# SIM800A.net
KiCad netlist of a schematic drawn in Altium Designer
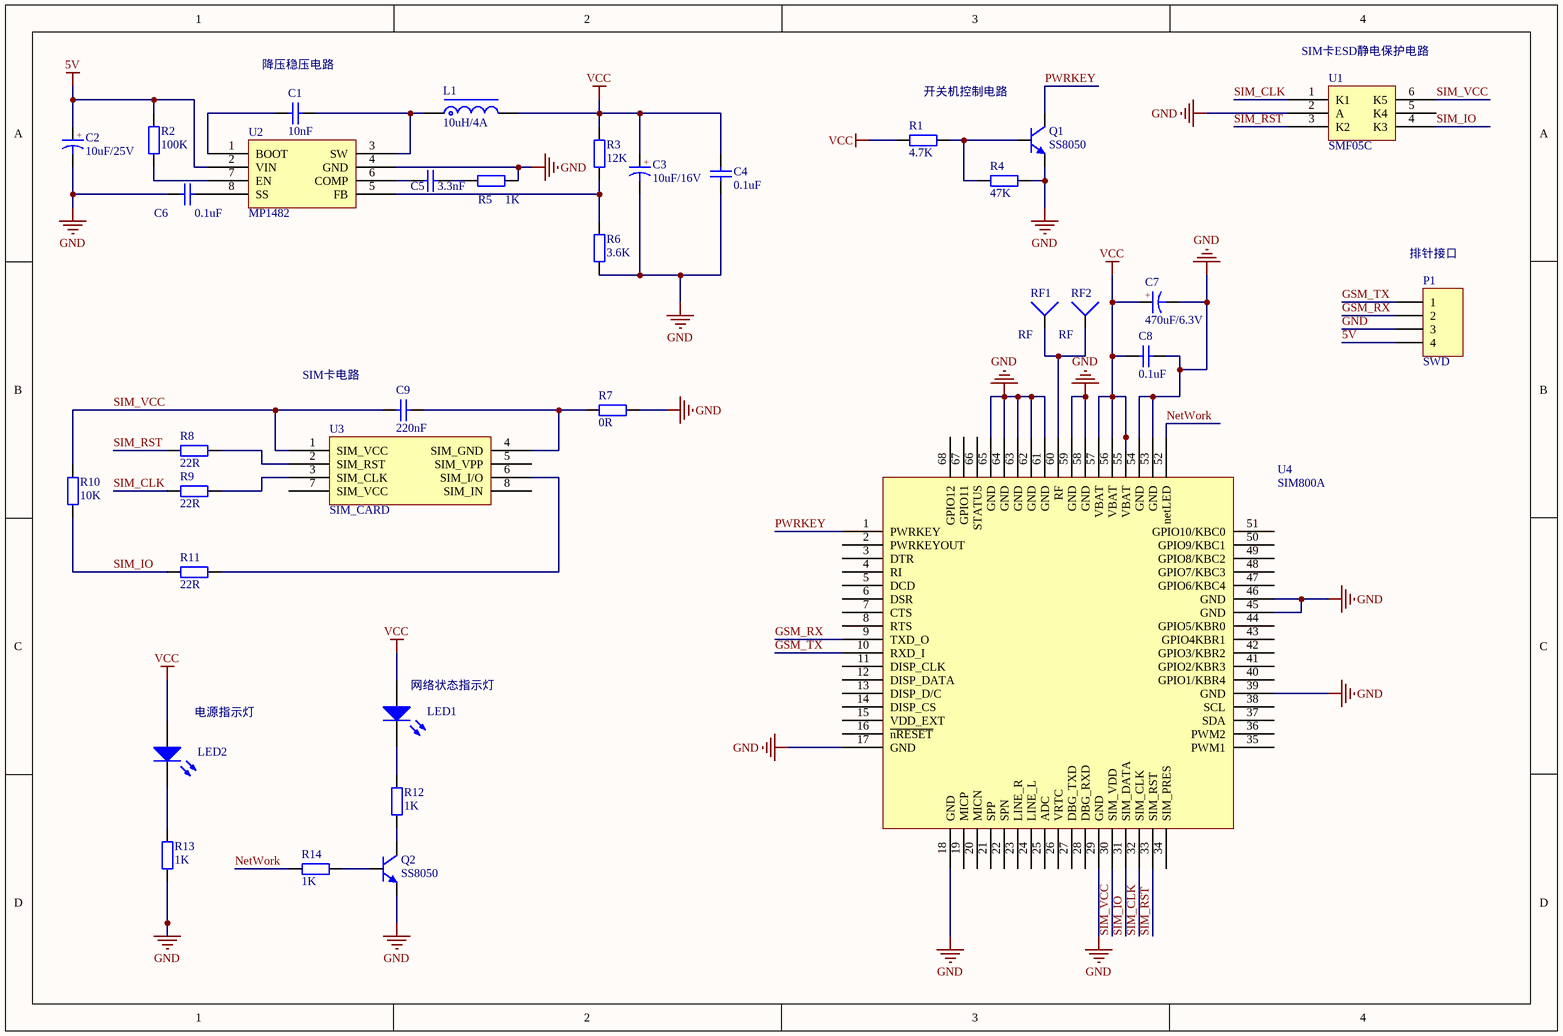
[diagram p0: SIM800A.SchDoc]

(export (version "E")
  (design (tool "Eeschema 10.0.6"))
  (components
    (comp (ref "C1")
      (value "10nF")
      (footprint "C0805_L")
      (description "贴片电容/MLCC电容")
      (libsource (lib "0.1 - 电阻-电容-电感-保险丝-晶振-晶体-磁珠-电位器-法拉电容-馈通电容") (part "C"))
    )
    (comp (ref "C2")
      (value "10uF/25V")
      (footprint "CE-1.5*4*8")
      (description "直插电解电容")
      (libsource (lib "0.1 - 电阻-电容-电感-保险丝-晶振-晶体-磁珠-电位器-法拉电容-馈通电容") (part "CE"))
    )
    (comp (ref "C3")
      (value "10uF/16V")
      (footprint "CE-1.5*4*8")
      (description "直插电解电容")
      (libsource (lib "0.1 - 电阻-电容-电感-保险丝-晶振-晶体-磁珠-电位器-法拉电容-馈通电容") (part "CE"))
    )
    (comp (ref "C4")
      (value "0.1uF")
      (footprint "C0805_L")
      (description "贴片电容/MLCC电容")
      (libsource (lib "0.1 - 电阻-电容-电感-保险丝-晶振-晶体-磁珠-电位器-法拉电容-馈通电容") (part "C"))
    )
    (comp (ref "C5")
      (value "3.3nF")
      (footprint "C0805_L")
      (description "贴片电容/MLCC电容")
      (libsource (lib "0.1 - 电阻-电容-电感-保险丝-晶振-晶体-磁珠-电位器-法拉电容-馈通电容") (part "C"))
    )
    (comp (ref "C6")
      (value "0.1uF")
      (footprint "C0805_L")
      (description "贴片电容/MLCC电容")
      (libsource (lib "0.1 - 电阻-电容-电感-保险丝-晶振-晶体-磁珠-电位器-法拉电容-馈通电容") (part "C"))
    )
    (comp (ref "C7")
      (value "470uF/6.3V")
      (footprint "CE-1.5*4*8")
      (description "直插电解电容")
      (libsource (lib "0.1 - 电阻-电容-电感-保险丝-晶振-晶体-磁珠-电位器-法拉电容-馈通电容") (part "CE"))
    )
    (comp (ref "C8")
      (value "0.1uF")
      (footprint "C0805_L")
      (description "贴片电容/MLCC电容")
      (libsource (lib "0.1 - 电阻-电容-电感-保险丝-晶振-晶体-磁珠-电位器-法拉电容-馈通电容") (part "C"))
    )
    (comp (ref "C9")
      (value "220nF")
      (footprint "C0805_L")
      (description "贴片电容/MLCC电容")
      (libsource (lib "0.1 - 电阻-电容-电感-保险丝-晶振-晶体-磁珠-电位器-法拉电容-馈通电容") (part "C"))
    )
    (comp (ref "L1")
      (value "10uH/4A")
      (footprint "LMR135")
      (description "功率磁环电感")
      (libsource (lib "0.1 - 电阻-电容-电感-保险丝-晶振-晶体-磁珠-电位器-法拉电容-馈通电容") (part "L-MR"))
    )
    (comp (ref "LED1")
      (value "红色")
      (footprint "LED0805_G")
      (description "贴片LED")
      (libsource (lib "0.3 - LED发光二极管-IR二极管_接收管-光耦") (part "LED"))
    )
    (comp (ref "LED2")
      (value "红色")
      (footprint "LED0805_G")
      (description "贴片LED")
      (libsource (lib "0.3 - LED发光二极管-IR二极管_接收管-光耦") (part "LED"))
    )
    (comp (ref "P1")
      (value "SWD")
      (footprint "HDR1X4")
      (description "Header, 4-Pin")
      (fields (field (name "PUBLISHER") "Altium Limited"))
      (libsource (lib "STM32F103C8T6") (part "Header 4"))
    )
    (comp (ref "Q1")
      (value "SS8050")
      (footprint "TO92A")
      (description "高频放大-NPN型")
      (libsource (lib "0.4 - 三极管-场效应管-可控硅") (part "8050-DIP"))
    )
    (comp (ref "Q2")
      (value "SS8050")
      (footprint "TO92A")
      (description "高频放大-NPN型")
      (libsource (lib "0.4 - 三极管-场效应管-可控硅") (part "8050-DIP"))
    )
    (comp (ref "R1")
      (value "4.7K")
      (footprint "R0805_L")
      (description "贴片电阻")
      (libsource (lib "0.1 - 电阻-电容-电感-保险丝-晶振-晶体-磁珠-电位器-法拉电容-馈通电容") (part "R"))
    )
    (comp (ref "R2")
      (value "100K")
      (footprint "R0805_L")
      (description "贴片电阻")
      (libsource (lib "0.1 - 电阻-电容-电感-保险丝-晶振-晶体-磁珠-电位器-法拉电容-馈通电容") (part "R"))
    )
    (comp (ref "R3")
      (value "12K")
      (footprint "R0805_L")
      (description "贴片电阻")
      (libsource (lib "0.1 - 电阻-电容-电感-保险丝-晶振-晶体-磁珠-电位器-法拉电容-馈通电容") (part "R"))
    )
    (comp (ref "R4")
      (value "47K")
      (footprint "R0805_L")
      (description "贴片电阻")
      (libsource (lib "0.1 - 电阻-电容-电感-保险丝-晶振-晶体-磁珠-电位器-法拉电容-馈通电容") (part "R"))
    )
    (comp (ref "R5")
      (value "1K")
      (footprint "R0805_L")
      (description "贴片电阻")
      (libsource (lib "0.1 - 电阻-电容-电感-保险丝-晶振-晶体-磁珠-电位器-法拉电容-馈通电容") (part "R"))
    )
    (comp (ref "R6")
      (value "3.6K")
      (footprint "R0805_L")
      (description "贴片电阻")
      (libsource (lib "0.1 - 电阻-电容-电感-保险丝-晶振-晶体-磁珠-电位器-法拉电容-馈通电容") (part "R"))
    )
    (comp (ref "R7")
      (value "0R")
      (footprint "R0805_L")
      (description "贴片电阻")
      (libsource (lib "0.1 - 电阻-电容-电感-保险丝-晶振-晶体-磁珠-电位器-法拉电容-馈通电容") (part "R"))
    )
    (comp (ref "R8")
      (value "22R")
      (footprint "R0805_L")
      (description "贴片电阻")
      (libsource (lib "0.1 - 电阻-电容-电感-保险丝-晶振-晶体-磁珠-电位器-法拉电容-馈通电容") (part "R"))
    )
    (comp (ref "R9")
      (value "22R")
      (footprint "R0805_L")
      (description "贴片电阻")
      (libsource (lib "0.1 - 电阻-电容-电感-保险丝-晶振-晶体-磁珠-电位器-法拉电容-馈通电容") (part "R"))
    )
    (comp (ref "R10")
      (value "10K")
      (footprint "R0805_L")
      (description "贴片电阻")
      (libsource (lib "0.1 - 电阻-电容-电感-保险丝-晶振-晶体-磁珠-电位器-法拉电容-馈通电容") (part "R"))
    )
    (comp (ref "R11")
      (value "22R")
      (footprint "R0805_L")
      (description "贴片电阻")
      (libsource (lib "0.1 - 电阻-电容-电感-保险丝-晶振-晶体-磁珠-电位器-法拉电容-馈通电容") (part "R"))
    )
    (comp (ref "R12")
      (value "1K")
      (footprint "R0805_L")
      (description "贴片电阻")
      (libsource (lib "0.1 - 电阻-电容-电感-保险丝-晶振-晶体-磁珠-电位器-法拉电容-馈通电容") (part "R"))
    )
    (comp (ref "R13")
      (value "1K")
      (footprint "R0805_L")
      (description "贴片电阻")
      (libsource (lib "0.1 - 电阻-电容-电感-保险丝-晶振-晶体-磁珠-电位器-法拉电容-馈通电容") (part "R"))
    )
    (comp (ref "R14")
      (value "1K")
      (footprint "R0805_L")
      (description "贴片电阻")
      (libsource (lib "0.1 - 电阻-电容-电感-保险丝-晶振-晶体-磁珠-电位器-法拉电容-馈通电容") (part "R"))
    )
    (comp (ref "RF1") (value "RF") (libsource (lib "SIM800A") (part "RF")))
    (comp (ref "RF2") (value "RF") (libsource (lib "SIM800A") (part "RF")))
    (comp (ref "U1") (value "SMF05C") (libsource (lib "SIM800A") (part "SMF05C")))
    (comp (ref "U2") (value "MP1482") (libsource (lib "SIM800A") (part "MP1482")))
    (comp (ref "U3") (value "SIM_CARD") (libsource (lib "SIM800A") (part "SIM_CARD")))
    (comp (ref "U4") (value "SIM800A") (libsource (lib "SIM800A") (part "SIM800A")))
  )
  (nets
    (net (code "1") (name "/GSM_RX") (class "Default")
      (node (ref "P1") (pin "2") (pinfunction "2_2") (pintype "passive"))
      (node (ref "U4") (pin "9") (pinfunction "TXD_O_9") (pintype "passive"))
    )
    (net (code "2") (name "/GSM_TX") (class "Default")
      (node (ref "P1") (pin "1") (pinfunction "1_1") (pintype "passive"))
      (node (ref "U4") (pin "10") (pinfunction "RXD_I_10") (pintype "passive"))
    )
    (net (code "3") (name "/NetWork") (class "Default")
      (node (ref "R14") (pin "2") (pinfunction "2_2") (pintype "passive"))
      (node (ref "U4") (pin "52") (pinfunction "netLED_52") (pintype "passive"))
    )
    (net (code "4") (name "/PWRKEY") (class "Default")
      (node (ref "Q1") (pin "3") (pinfunction "C_3") (pintype "passive"))
      (node (ref "U4") (pin "1") (pinfunction "PWRKEY_1") (pintype "passive"))
    )
    (net (code "5") (name "/SIM_CLK") (class "Default")
      (node (ref "R9") (pin "2") (pinfunction "2_2") (pintype "passive"))
      (node (ref "U1") (pin "1") (pinfunction "K1_1") (pintype "passive"))
      (node (ref "U4") (pin "32") (pinfunction "SIM_CLK_32") (pintype "passive"))
    )
    (net (code "6") (name "/SIM_IO") (class "Default")
      (node (ref "R10") (pin "2") (pinfunction "2_2") (pintype "passive"))
      (node (ref "R11") (pin "2") (pinfunction "2_2") (pintype "passive"))
      (node (ref "U1") (pin "4") (pinfunction "K3_4") (pintype "passive"))
      (node (ref "U4") (pin "31") (pinfunction "SIM_DATA_31") (pintype "passive"))
    )
    (net (code "7") (name "/SIM_RST") (class "Default")
      (node (ref "R8") (pin "2") (pinfunction "2_2") (pintype "passive"))
      (node (ref "U1") (pin "3") (pinfunction "K2_3") (pintype "passive"))
      (node (ref "U4") (pin "33") (pinfunction "SIM_RST_33") (pintype "passive"))
    )
    (net (code "8") (name "/SIM_VCC") (class "Default")
      (node (ref "C9") (pin "2") (pinfunction "2_2") (pintype "passive"))
      (node (ref "R10") (pin "1") (pinfunction "1_1") (pintype "passive"))
      (node (ref "U1") (pin "6") (pinfunction "K5_6") (pintype "passive"))
      (node (ref "U3") (pin "1") (pinfunction "SIM_VCC_1") (pintype "passive"))
      (node (ref "U4") (pin "30") (pinfunction "SIM_VDD_30") (pintype "passive"))
    )
    (net (code "9") (name "5V") (class "Default")
      (node (ref "C2") (pin "1") (pinfunction "1_1") (pintype "passive"))
      (node (ref "P1") (pin "4") (pinfunction "4_4") (pintype "passive"))
      (node (ref "R2") (pin "2") (pinfunction "2_2") (pintype "passive"))
      (node (ref "U2") (pin "2") (pinfunction "VIN_2") (pintype "passive"))
    )
    (net (code "10") (name "GND") (class "Default")
      (node (ref "C2") (pin "2") (pinfunction "2_2") (pintype "passive"))
      (node (ref "C3") (pin "2") (pinfunction "2_2") (pintype "passive"))
      (node (ref "C4") (pin "1") (pinfunction "1_1") (pintype "passive"))
      (node (ref "C6") (pin "1") (pinfunction "1_1") (pintype "passive"))
      (node (ref "C7") (pin "2") (pinfunction "2_2") (pintype "passive"))
      (node (ref "C8") (pin "2") (pinfunction "2_2") (pintype "passive"))
      (node (ref "P1") (pin "3") (pinfunction "3_3") (pintype "passive"))
      (node (ref "Q1") (pin "1") (pinfunction "E_1") (pintype "passive"))
      (node (ref "Q2") (pin "1") (pinfunction "E_1") (pintype "passive"))
      (node (ref "R13") (pin "1") (pinfunction "1_1") (pintype "passive"))
      (node (ref "R4") (pin "1") (pinfunction "1_1") (pintype "passive"))
      (node (ref "R5") (pin "2") (pinfunction "2_2") (pintype "passive"))
      (node (ref "R6") (pin "1") (pinfunction "1_1") (pintype "passive"))
      (node (ref "R7") (pin "1") (pinfunction "1_1") (pintype "passive"))
      (node (ref "U1") (pin "2") (pinfunction "A_2") (pintype "passive"))
      (node (ref "U2") (pin "4") (pinfunction "GND_4") (pintype "passive"))
      (node (ref "U4") (pin "17") (pinfunction "GND_17") (pintype "passive"))
      (node (ref "U4") (pin "18") (pinfunction "GND_18") (pintype "passive"))
      (node (ref "U4") (pin "29") (pinfunction "GND_29") (pintype "passive"))
      (node (ref "U4") (pin "39") (pinfunction "GND_39") (pintype "passive"))
      (node (ref "U4") (pin "45") (pinfunction "GND_45") (pintype "passive"))
      (node (ref "U4") (pin "46") (pinfunction "GND_46") (pintype "passive"))
      (node (ref "U4") (pin "53") (pinfunction "GND_53") (pintype "passive"))
      (node (ref "U4") (pin "54") (pinfunction "GND_54") (pintype "passive"))
      (node (ref "U4") (pin "58") (pinfunction "GND_58") (pintype "passive"))
      (node (ref "U4") (pin "59") (pinfunction "GND_59") (pintype "passive"))
      (node (ref "U4") (pin "61") (pinfunction "GND_61") (pintype "passive"))
      (node (ref "U4") (pin "62") (pinfunction "GND_62") (pintype "passive"))
      (node (ref "U4") (pin "63") (pinfunction "GND_63") (pintype "passive"))
      (node (ref "U4") (pin "64") (pinfunction "GND_64") (pintype "passive"))
      (node (ref "U4") (pin "65") (pinfunction "GND_65") (pintype "passive"))
    )
    (net (code "11") (name "Net-(C5-Pad2)") (class "Default")
      (node (ref "C5") (pin "2") (pinfunction "2_2") (pintype "passive"))
      (node (ref "R5") (pin "1") (pinfunction "1_1") (pintype "passive"))
    )
    (net (code "12") (name "Net-(LED1-K)") (class "Default")
      (node (ref "LED1") (pin "2") (pinfunction "K_2") (pintype "passive"))
      (node (ref "R12") (pin "2") (pinfunction "2_2") (pintype "passive"))
    )
    (net (code "13") (name "Net-(LED2-K)") (class "Default")
      (node (ref "LED2") (pin "2") (pinfunction "K_2") (pintype "passive"))
      (node (ref "R13") (pin "2") (pinfunction "2_2") (pintype "passive"))
    )
    (net (code "14") (name "Net-(Q1-B)") (class "Default")
      (node (ref "Q1") (pin "2") (pinfunction "B_2") (pintype "passive"))
      (node (ref "R1") (pin "1") (pinfunction "1_1") (pintype "passive"))
      (node (ref "R4") (pin "2") (pinfunction "2_2") (pintype "passive"))
    )
    (net (code "15") (name "Net-(Q2-B)") (class "Default")
      (node (ref "Q2") (pin "2") (pinfunction "B_2") (pintype "passive"))
      (node (ref "R14") (pin "1") (pinfunction "1_1") (pintype "passive"))
    )
    (net (code "16") (name "Net-(Q2-C)") (class "Default")
      (node (ref "Q2") (pin "3") (pinfunction "C_3") (pintype "passive"))
      (node (ref "R12") (pin "1") (pinfunction "1_1") (pintype "passive"))
    )
    (net (code "17") (name "Net-(U2-BOOT)") (class "Default")
      (node (ref "C1") (pin "1") (pinfunction "1_1") (pintype "passive"))
      (node (ref "U2") (pin "1") (pinfunction "BOOT_1") (pintype "passive"))
    )
    (net (code "18") (name "Net-(U2-COMP)") (class "Default")
      (node (ref "C5") (pin "1") (pinfunction "1_1") (pintype "passive"))
      (node (ref "U2") (pin "6") (pinfunction "COMP_6") (pintype "passive"))
    )
    (net (code "19") (name "Net-(U2-EN)") (class "Default")
      (node (ref "R2") (pin "1") (pinfunction "1_1") (pintype "passive"))
      (node (ref "U2") (pin "7") (pinfunction "EN_7") (pintype "passive"))
    )
    (net (code "20") (name "Net-(U2-FB)") (class "Default")
      (node (ref "R3") (pin "1") (pinfunction "1_1") (pintype "passive"))
      (node (ref "R6") (pin "2") (pinfunction "2_2") (pintype "passive"))
      (node (ref "U2") (pin "5") (pinfunction "FB_5") (pintype "passive"))
    )
    (net (code "21") (name "Net-(U2-SS)") (class "Default")
      (node (ref "C6") (pin "2") (pinfunction "2_2") (pintype "passive"))
      (node (ref "U2") (pin "8") (pinfunction "SS_8") (pintype "passive"))
    )
    (net (code "22") (name "Net-(U2-SW)") (class "Default")
      (node (ref "C1") (pin "2") (pinfunction "2_2") (pintype "passive"))
      (node (ref "L1") (pin "1") (pinfunction "1_1") (pintype "passive"))
      (node (ref "U2") (pin "3") (pinfunction "SW_3") (pintype "passive"))
    )
    (net (code "23") (name "Net-(U3-SIM_CLK)") (class "Default")
      (node (ref "R9") (pin "1") (pinfunction "1_1") (pintype "passive"))
      (node (ref "U3") (pin "3") (pinfunction "SIM_CLK_3") (pintype "passive"))
    )
    (net (code "24") (name "Net-(U3-SIM_GND)") (class "Default")
      (node (ref "C9") (pin "1") (pinfunction "1_1") (pintype "passive"))
      (node (ref "R7") (pin "2") (pinfunction "2_2") (pintype "passive"))
      (node (ref "U3") (pin "4") (pinfunction "SIM_GND_4") (pintype "passive"))
    )
    (net (code "25") (name "Net-(U3-SIM_I{slash}O)") (class "Default")
      (node (ref "R11") (pin "1") (pinfunction "1_1") (pintype "passive"))
      (node (ref "U3") (pin "6") (pinfunction "SIM_I/O_6") (pintype "passive"))
    )
    (net (code "26") (name "Net-(U3-SIM_RST)") (class "Default")
      (node (ref "R8") (pin "1") (pinfunction "1_1") (pintype "passive"))
      (node (ref "U3") (pin "2") (pinfunction "SIM_RST_2") (pintype "passive"))
    )
    (net (code "27") (name "VCC") (class "Default")
      (node (ref "C3") (pin "1") (pinfunction "1_1") (pintype "passive"))
      (node (ref "C4") (pin "2") (pinfunction "2_2") (pintype "passive"))
      (node (ref "C7") (pin "1") (pinfunction "1_1") (pintype "passive"))
      (node (ref "C8") (pin "1") (pinfunction "1_1") (pintype "passive"))
      (node (ref "L1") (pin "2") (pinfunction "2_2") (pintype "passive"))
      (node (ref "LED1") (pin "1") (pinfunction "A_1") (pintype "passive"))
      (node (ref "LED2") (pin "1") (pinfunction "A_1") (pintype "passive"))
      (node (ref "R1") (pin "2") (pinfunction "2_2") (pintype "passive"))
      (node (ref "R3") (pin "2") (pinfunction "2_2") (pintype "passive"))
      (node (ref "U4") (pin "55") (pinfunction "VBAT_55") (pintype "passive"))
      (node (ref "U4") (pin "56") (pinfunction "VBAT_56") (pintype "passive"))
      (node (ref "U4") (pin "57") (pinfunction "VBAT_57") (pintype "passive"))
    )
    (net (code "28") (name "unconnected-(U1-K4-Pad5)") (class "Default")
      (node (ref "U1") (pin "5") (pinfunction "K4_5") (pintype "passive"))
    )
    (net (code "29") (name "unconnected-(U3-SIM_IN-Pad8)") (class "Default")
      (node (ref "U3") (pin "8") (pinfunction "SIM_IN_8") (pintype "passive"))
    )
    (net (code "30") (name "unconnected-(U3-SIM_VCC-Pad7)") (class "Default")
      (node (ref "U3") (pin "7") (pinfunction "SIM_VCC_7") (pintype "passive"))
    )
    (net (code "31") (name "unconnected-(U3-SIM_VPP-Pad5)") (class "Default")
      (node (ref "U3") (pin "5") (pinfunction "SIM_VPP_5") (pintype "passive"))
    )
    (net (code "32") (name "unconnected-(U4-ADC-Pad25)") (class "Default")
      (node (ref "U4") (pin "25") (pinfunction "ADC_25") (pintype "passive"))
    )
    (net (code "33") (name "unconnected-(U4-CTS-Pad7)") (class "Default")
      (node (ref "U4") (pin "7") (pinfunction "CTS_7") (pintype "passive"))
    )
    (net (code "34") (name "unconnected-(U4-DBG_RXD-Pad28)") (class "Default")
      (node (ref "U4") (pin "28") (pinfunction "DBG_RXD_28") (pintype "passive"))
    )
    (net (code "35") (name "unconnected-(U4-DBG_TXD-Pad27)") (class "Default")
      (node (ref "U4") (pin "27") (pinfunction "DBG_TXD_27") (pintype "passive"))
    )
    (net (code "36") (name "unconnected-(U4-DCD-Pad5)") (class "Default")
      (node (ref "U4") (pin "5") (pinfunction "DCD_5") (pintype "passive"))
    )
    (net (code "37") (name "unconnected-(U4-DISP_CLK-Pad11)") (class "Default")
      (node (ref "U4") (pin "11") (pinfunction "DISP_CLK_11") (pintype "passive"))
    )
    (net (code "38") (name "unconnected-(U4-DISP_CS-Pad14)") (class "Default")
      (node (ref "U4") (pin "14") (pinfunction "DISP_CS_14") (pintype "passive"))
    )
    (net (code "39") (name "unconnected-(U4-DISP_DATA-Pad12)") (class "Default")
      (node (ref "U4") (pin "12") (pinfunction "DISP_DATA_12") (pintype "passive"))
    )
    (net (code "40") (name "unconnected-(U4-DISP_D{slash}C-Pad13)") (class "Default")
      (node (ref "U4") (pin "13") (pinfunction "DISP_D/C_13") (pintype "passive"))
    )
    (net (code "41") (name "unconnected-(U4-DSR-Pad6)") (class "Default")
      (node (ref "U4") (pin "6") (pinfunction "DSR_6") (pintype "passive"))
    )
    (net (code "42") (name "unconnected-(U4-DTR-Pad3)") (class "Default")
      (node (ref "U4") (pin "3") (pinfunction "DTR_3") (pintype "passive"))
    )
    (net (code "43") (name "unconnected-(U4-GPIO1{slash}KBR4-Pad40)") (class "Default")
      (node (ref "U4") (pin "40") (pinfunction "GPIO1/KBR4_40") (pintype "passive"))
    )
    (net (code "44") (name "unconnected-(U4-GPIO2{slash}KBR3-Pad41)") (class "Default")
      (node (ref "U4") (pin "41") (pinfunction "GPIO2/KBR3_41") (pintype "passive"))
    )
    (net (code "45") (name "unconnected-(U4-GPIO3{slash}KBR2-Pad42)") (class "Default")
      (node (ref "U4") (pin "42") (pinfunction "GPIO3/KBR2_42") (pintype "passive"))
    )
    (net (code "46") (name "unconnected-(U4-GPIO4KBR1-Pad43)") (class "Default")
      (node (ref "U4") (pin "43") (pinfunction "GPIO4KBR1_43") (pintype "passive"))
    )
    (net (code "47") (name "unconnected-(U4-GPIO5{slash}KBR0-Pad44)") (class "Default")
      (node (ref "U4") (pin "44") (pinfunction "GPIO5/KBR0_44") (pintype "passive"))
    )
    (net (code "48") (name "unconnected-(U4-GPIO6{slash}KBC4-Pad47)") (class "Default")
      (node (ref "U4") (pin "47") (pinfunction "GPIO6/KBC4_47") (pintype "passive"))
    )
    (net (code "49") (name "unconnected-(U4-GPIO7{slash}KBC3-Pad48)") (class "Default")
      (node (ref "U4") (pin "48") (pinfunction "GPIO7/KBC3_48") (pintype "passive"))
    )
    (net (code "50") (name "unconnected-(U4-GPIO8{slash}KBC2-Pad49)") (class "Default")
      (node (ref "U4") (pin "49") (pinfunction "GPIO8/KBC2_49") (pintype "passive"))
    )
    (net (code "51") (name "unconnected-(U4-GPIO9{slash}KBC1-Pad50)") (class "Default")
      (node (ref "U4") (pin "50") (pinfunction "GPIO9/KBC1_50") (pintype "passive"))
    )
    (net (code "52") (name "unconnected-(U4-GPIO10{slash}KBC0-Pad51)") (class "Default")
      (node (ref "U4") (pin "51") (pinfunction "GPIO10/KBC0_51") (pintype "passive"))
    )
    (net (code "53") (name "unconnected-(U4-GPIO11-Pad67)") (class "Default")
      (node (ref "U4") (pin "67") (pinfunction "GPIO11_67") (pintype "passive"))
    )
    (net (code "54") (name "unconnected-(U4-GPIO12-Pad68)") (class "Default")
      (node (ref "U4") (pin "68") (pinfunction "GPIO12_68") (pintype "passive"))
    )
    (net (code "55") (name "unconnected-(U4-LINE_L-Pad24)") (class "Default")
      (node (ref "U4") (pin "24") (pinfunction "LINE_L_24") (pintype "passive"))
    )
    (net (code "56") (name "unconnected-(U4-LINE_R-Pad23)") (class "Default")
      (node (ref "U4") (pin "23") (pinfunction "LINE_R_23") (pintype "passive"))
    )
    (net (code "57") (name "unconnected-(U4-MICN-Pad20)") (class "Default")
      (node (ref "U4") (pin "20") (pinfunction "MICN_20") (pintype "passive"))
    )
    (net (code "58") (name "unconnected-(U4-MICP-Pad19)") (class "Default")
      (node (ref "U4") (pin "19") (pinfunction "MICP_19") (pintype "passive"))
    )
    (net (code "59") (name "unconnected-(U4-PWM1-Pad35)") (class "Default")
      (node (ref "U4") (pin "35") (pinfunction "PWM1_35") (pintype "passive"))
    )
    (net (code "60") (name "unconnected-(U4-PWM2-Pad36)") (class "Default")
      (node (ref "U4") (pin "36") (pinfunction "PWM2_36") (pintype "passive"))
    )
    (net (code "61") (name "unconnected-(U4-PWRKEYOUT-Pad2)") (class "Default")
      (node (ref "U4") (pin "2") (pinfunction "PWRKEYOUT_2") (pintype "passive"))
    )
    (net (code "62") (name "unconnected-(U4-RF-Pad60)") (class "Default")
      (node (ref "U4") (pin "60") (pinfunction "RF_60") (pintype "passive"))
    )
    (net (code "63") (name "unconnected-(U4-RI-Pad4)") (class "Default")
      (node (ref "U4") (pin "4") (pinfunction "RI_4") (pintype "passive"))
    )
    (net (code "64") (name "unconnected-(U4-RTS-Pad8)") (class "Default")
      (node (ref "U4") (pin "8") (pinfunction "RTS_8") (pintype "passive"))
    )
    (net (code "65") (name "unconnected-(U4-SCL-Pad38)") (class "Default")
      (node (ref "U4") (pin "38") (pinfunction "SCL_38") (pintype "passive"))
    )
    (net (code "66") (name "unconnected-(U4-SDA-Pad37)") (class "Default")
      (node (ref "U4") (pin "37") (pinfunction "SDA_37") (pintype "passive"))
    )
    (net (code "67") (name "unconnected-(U4-SIM_PRES-Pad34)") (class "Default")
      (node (ref "U4") (pin "34") (pinfunction "SIM_PRES_34") (pintype "passive"))
    )
    (net (code "68") (name "unconnected-(U4-SPN-Pad22)") (class "Default")
      (node (ref "U4") (pin "22") (pinfunction "SPN_22") (pintype "passive"))
    )
    (net (code "69") (name "unconnected-(U4-SPP-Pad21)") (class "Default")
      (node (ref "U4") (pin "21") (pinfunction "SPP_21") (pintype "passive"))
    )
    (net (code "70") (name "unconnected-(U4-STATUS-Pad66)") (class "Default")
      (node (ref "U4") (pin "66") (pinfunction "STATUS_66") (pintype "passive"))
    )
    (net (code "71") (name "unconnected-(U4-VDD_EXT-Pad15)") (class "Default")
      (node (ref "U4") (pin "15") (pinfunction "VDD_EXT_15") (pintype "passive"))
    )
    (net (code "72") (name "unconnected-(U4-VRTC-Pad26)") (class "Default")
      (node (ref "U4") (pin "26") (pinfunction "VRTC_26") (pintype "passive"))
    )
    (net (code "73") (name "unconnected-(U4-~{nRESET}-Pad16)") (class "Default")
      (node (ref "U4") (pin "16") (pinfunction "~{nRESET}_16") (pintype "passive"))
    )
  )
)
